# nixi_board.net
KiCad netlist of a schematic drawn in EAGLE
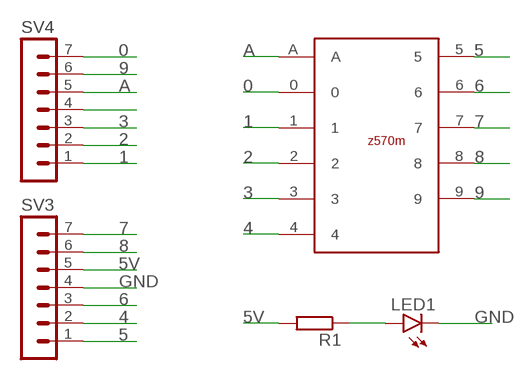
[diagram p0: schematic, sheet 1]

(export (version "E")
  (design (tool "Eeschema 10.0.6"))
  (components
    (comp (ref "LED1")
      (value "LEDSMT1206")
      (footprint "eagle-import:1206")
      (libsource (lib "eagle-import") (part "LEDSMT1206"))
    )
    (comp (ref "R1")
      (value "R-EU_R1206")
      (footprint "eagle-import:R1206")
      (libsource (lib "eagle-import") (part "R-EU_R1206"))
    )
    (comp (ref "SV3")
      (value "MA07-1")
      (footprint "eagle-import:MA07-1")
      (libsource (lib "eagle-import") (part "MA07-1"))
    )
    (comp (ref "SV4")
      (value "MA07-1")
      (footprint "eagle-import:MA07-1")
      (libsource (lib "eagle-import") (part "MA07-1"))
    )
    (comp (ref "U$1")
      (value "Z570M")
      (footprint "eagle-import:Z570M")
      (libsource (lib "eagle-import") (part "Z570M"))
    )
  )
  (nets
    (net (code "1") (name "/0") (class "Default")
      (node (ref "SV4") (pin "7") (pinfunction "7_7") (pintype "passive"))
      (node (ref "U$1") (pin "0") (pinfunction "0_0") (pintype "bidirectional"))
    )
    (net (code "2") (name "/1") (class "Default")
      (node (ref "SV4") (pin "1") (pinfunction "1_1") (pintype "passive"))
      (node (ref "U$1") (pin "1") (pinfunction "1_1") (pintype "bidirectional"))
    )
    (net (code "3") (name "/2") (class "Default")
      (node (ref "SV4") (pin "2") (pinfunction "2_2") (pintype "passive"))
      (node (ref "U$1") (pin "2") (pinfunction "2_2") (pintype "bidirectional"))
    )
    (net (code "4") (name "/3") (class "Default")
      (node (ref "SV4") (pin "3") (pinfunction "3_3") (pintype "passive"))
      (node (ref "U$1") (pin "3") (pinfunction "3_3") (pintype "bidirectional"))
    )
    (net (code "5") (name "/4") (class "Default")
      (node (ref "SV3") (pin "2") (pinfunction "2_2") (pintype "passive"))
      (node (ref "U$1") (pin "4") (pinfunction "4_4") (pintype "bidirectional"))
    )
    (net (code "6") (name "/5") (class "Default")
      (node (ref "SV3") (pin "1") (pinfunction "1_1") (pintype "passive"))
      (node (ref "U$1") (pin "5") (pinfunction "5_5") (pintype "bidirectional"))
    )
    (net (code "7") (name "/5V") (class "Default")
      (node (ref "R1") (pin "2") (pinfunction "2_2") (pintype "passive"))
      (node (ref "SV3") (pin "5") (pinfunction "5_5") (pintype "passive"))
    )
    (net (code "8") (name "/6") (class "Default")
      (node (ref "SV3") (pin "3") (pinfunction "3_3") (pintype "passive"))
      (node (ref "U$1") (pin "6") (pinfunction "6_6") (pintype "bidirectional"))
    )
    (net (code "9") (name "/7") (class "Default")
      (node (ref "SV3") (pin "7") (pinfunction "7_7") (pintype "passive"))
      (node (ref "U$1") (pin "7") (pinfunction "7_7") (pintype "bidirectional"))
    )
    (net (code "10") (name "/8") (class "Default")
      (node (ref "SV3") (pin "6") (pinfunction "6_6") (pintype "passive"))
      (node (ref "U$1") (pin "8") (pinfunction "8_8") (pintype "bidirectional"))
    )
    (net (code "11") (name "/9") (class "Default")
      (node (ref "SV4") (pin "6") (pinfunction "6_6") (pintype "passive"))
      (node (ref "U$1") (pin "9") (pinfunction "9_9") (pintype "bidirectional"))
    )
    (net (code "12") (name "/A") (class "Default")
      (node (ref "SV4") (pin "5") (pinfunction "5_5") (pintype "passive"))
      (node (ref "U$1") (pin "A") (pinfunction "A_A") (pintype "bidirectional"))
    )
    (net (code "13") (name "/GND") (class "Default")
      (node (ref "LED1") (pin "C") (pinfunction "C_C") (pintype "passive"))
      (node (ref "SV3") (pin "4") (pinfunction "4_4") (pintype "passive"))
    )
    (net (code "14") (name "Net-(LED1-PadA)") (class "Default")
      (node (ref "LED1") (pin "A") (pinfunction "A_A") (pintype "passive"))
      (node (ref "R1") (pin "1") (pinfunction "1_1") (pintype "passive"))
    )
    (net (code "15") (name "unconnected-(SV4-Pad4)") (class "Default")
      (node (ref "SV4") (pin "4") (pinfunction "4_4") (pintype "passive"))
    )
  )
)
